# arduino_due_component_connection_2.net
KiCad netlist of a schematic drawn in Altium Designer
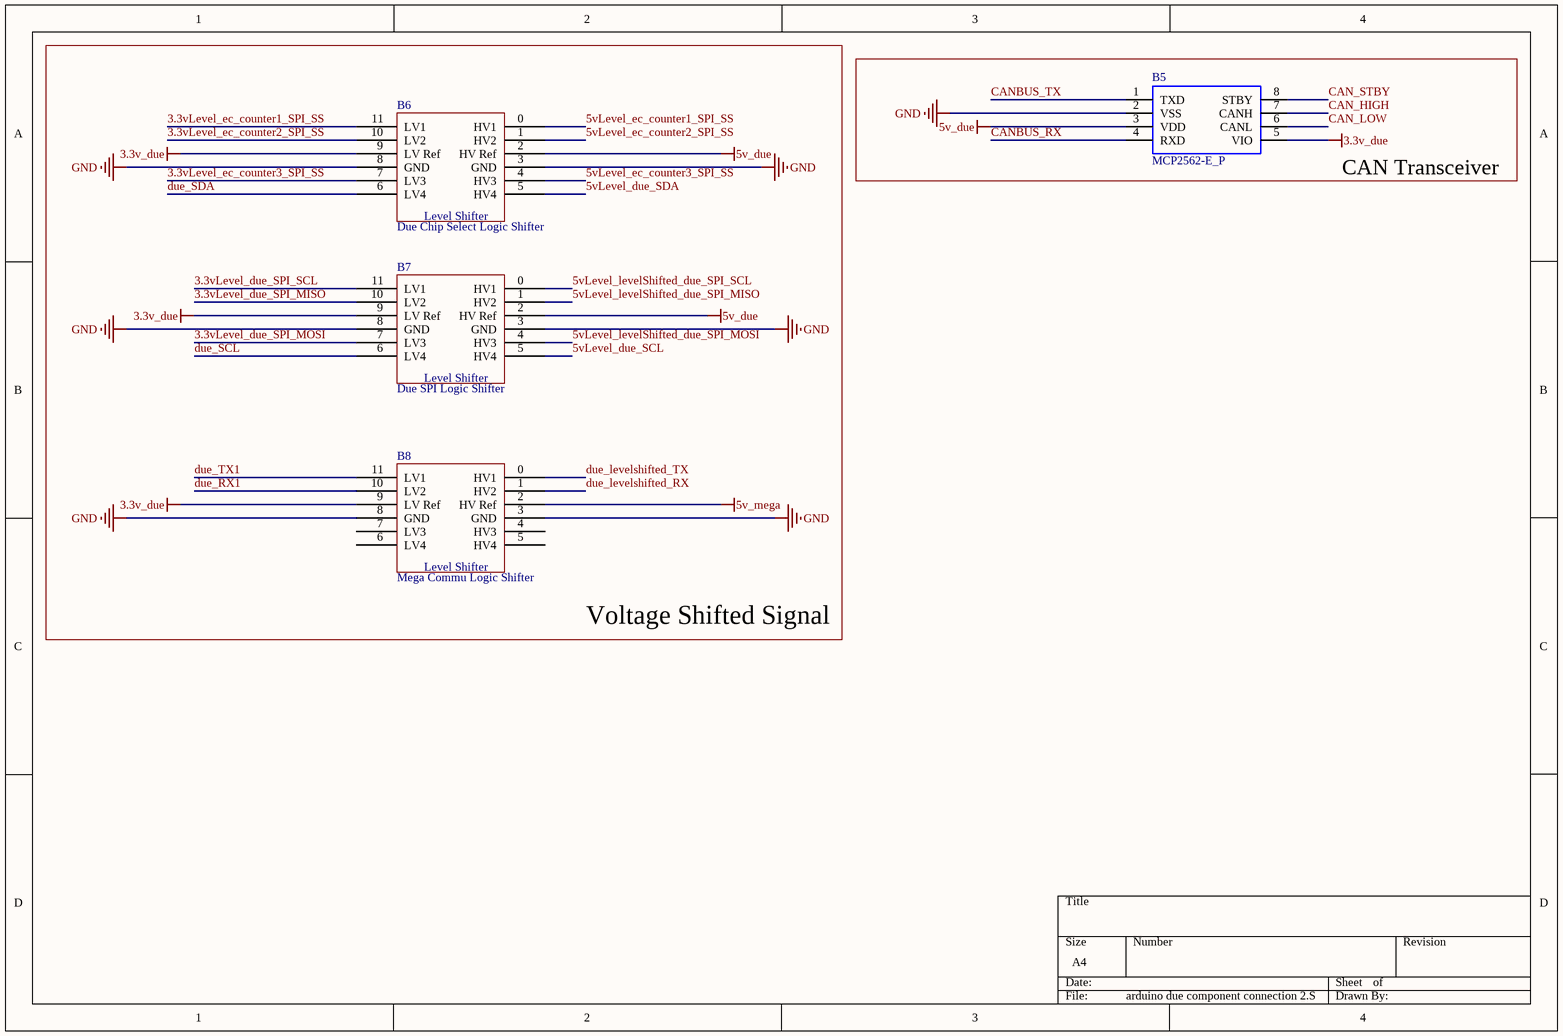
[diagram p0: arduino due component connection 2.SchDoc]

(export (version "E")
  (design (tool "Eeschema 10.0.6"))
  (components
    (comp (ref "B5")
      (value "MCP2562-E_P")
      (footprint "DIP781W56P254L950H533Q8N")
      (fields
        (field (name "RS PART NUMBER") "7990225")
        (field (name "MANUFACTURER_PART_NUMBER") "MCP2562-E/P")
      )
      (libsource (lib "MCP2562-E_P") (part "MCP2562-E_P"))
    )
    (comp (ref "B6")
      (value "Level Shifter 4 Channel")
      (footprint "level shifter 4C:level shifter 4C")
      (fields (field (name "USAGE") "Due Chip Select Logic Shifter"))
      (libsource (lib "level shifter 4C") (part "Level Shifter 4 Channel"))
    )
    (comp (ref "B7")
      (value "Level Shifter 4 Channel")
      (footprint "level shifter 4C:level shifter 4C")
      (fields (field (name "USAGE") "Due SPI Logic Shifter"))
      (libsource (lib "level shifter 4C") (part "Level Shifter 4 Channel"))
    )
    (comp (ref "B8")
      (value "Level Shifter 4 Channel")
      (footprint "level shifter 4C:level shifter 4C")
      (fields (field (name "USAGE") "Mega Commu Logic Shifter"))
      (libsource (lib "level shifter 4C") (part "Level Shifter 4 Channel"))
    )
  )
  (nets
    (net (code "1") (name "/3.3vLevel_due_SPI_MISO") (class "Default")
      (node (ref "B7") (pin "10") (pinfunction "LV2_10") (pintype "passive"))
    )
    (net (code "2") (name "/3.3vLevel_due_SPI_MOSI") (class "Default")
      (node (ref "B7") (pin "7") (pinfunction "LV3_7") (pintype "passive"))
    )
    (net (code "3") (name "/3.3vLevel_due_SPI_SCL") (class "Default")
      (node (ref "B7") (pin "11") (pinfunction "LV1_11") (pintype "passive"))
    )
    (net (code "4") (name "/3.3vLevel_ec_counter1_SPI_SS") (class "Default")
      (node (ref "B6") (pin "11") (pinfunction "LV1_11") (pintype "passive"))
    )
    (net (code "5") (name "/3.3vLevel_ec_counter2_SPI_SS") (class "Default")
      (node (ref "B6") (pin "10") (pinfunction "LV2_10") (pintype "passive"))
    )
    (net (code "6") (name "/3.3vLevel_ec_counter3_SPI_SS") (class "Default")
      (node (ref "B6") (pin "7") (pinfunction "LV3_7") (pintype "passive"))
    )
    (net (code "7") (name "/5vLevel_due_SCL") (class "Default")
      (node (ref "B7") (pin "5") (pinfunction "HV4_5") (pintype "passive"))
    )
    (net (code "8") (name "/5vLevel_due_SDA") (class "Default")
      (node (ref "B6") (pin "5") (pinfunction "HV4_5") (pintype "passive"))
    )
    (net (code "9") (name "/5vLevel_ec_counter1_SPI_SS") (class "Default")
      (node (ref "B6") (pin "0") (pinfunction "HV1_0") (pintype "passive"))
    )
    (net (code "10") (name "/5vLevel_ec_counter2_SPI_SS") (class "Default")
      (node (ref "B6") (pin "1") (pinfunction "HV2_1") (pintype "passive"))
    )
    (net (code "11") (name "/5vLevel_ec_counter3_SPI_SS") (class "Default")
      (node (ref "B6") (pin "4") (pinfunction "HV3_4") (pintype "passive"))
    )
    (net (code "12") (name "/5vLevel_levelShifted_due_SPI_MISO") (class "Default")
      (node (ref "B7") (pin "1") (pinfunction "HV2_1") (pintype "passive"))
    )
    (net (code "13") (name "/5vLevel_levelShifted_due_SPI_MOSI") (class "Default")
      (node (ref "B7") (pin "4") (pinfunction "HV3_4") (pintype "passive"))
    )
    (net (code "14") (name "/5vLevel_levelShifted_due_SPI_SCL") (class "Default")
      (node (ref "B7") (pin "0") (pinfunction "HV1_0") (pintype "passive"))
    )
    (net (code "15") (name "/CANBUS_RX") (class "Default")
      (node (ref "B5") (pin "4") (pinfunction "RXD_4") (pintype "passive"))
    )
    (net (code "16") (name "/CANBUS_TX") (class "Default")
      (node (ref "B5") (pin "1") (pinfunction "TXD_1") (pintype "passive"))
    )
    (net (code "17") (name "/CAN_HIGH") (class "Default")
      (node (ref "B5") (pin "7") (pinfunction "CANH_7") (pintype "passive"))
    )
    (net (code "18") (name "/CAN_LOW") (class "Default")
      (node (ref "B5") (pin "6") (pinfunction "CANL_6") (pintype "passive"))
    )
    (net (code "19") (name "/CAN_STBY") (class "Default")
      (node (ref "B5") (pin "8") (pinfunction "STBY_8") (pintype "passive"))
    )
    (net (code "20") (name "/due_RX1") (class "Default")
      (node (ref "B8") (pin "10") (pinfunction "LV2_10") (pintype "passive"))
    )
    (net (code "21") (name "/due_SCL") (class "Default")
      (node (ref "B7") (pin "6") (pinfunction "LV4_6") (pintype "passive"))
    )
    (net (code "22") (name "/due_SDA") (class "Default")
      (node (ref "B6") (pin "6") (pinfunction "LV4_6") (pintype "passive"))
    )
    (net (code "23") (name "/due_TX1") (class "Default")
      (node (ref "B8") (pin "11") (pinfunction "LV1_11") (pintype "passive"))
    )
    (net (code "24") (name "/due_levelshifted_RX") (class "Default")
      (node (ref "B8") (pin "1") (pinfunction "HV2_1") (pintype "passive"))
    )
    (net (code "25") (name "/due_levelshifted_TX") (class "Default")
      (node (ref "B8") (pin "0") (pinfunction "HV1_0") (pintype "passive"))
    )
    (net (code "26") (name "3.3v_due") (class "Default")
      (node (ref "B5") (pin "5") (pinfunction "VIO_5") (pintype "passive"))
      (node (ref "B6") (pin "9") (pinfunction "LV_Ref_9") (pintype "passive"))
      (node (ref "B7") (pin "9") (pinfunction "LV_Ref_9") (pintype "passive"))
      (node (ref "B8") (pin "9") (pinfunction "LV_Ref_9") (pintype "passive"))
    )
    (net (code "27") (name "5v_due") (class "Default")
      (node (ref "B5") (pin "3") (pinfunction "VDD_3") (pintype "passive"))
      (node (ref "B6") (pin "2") (pinfunction "HV_Ref_2") (pintype "passive"))
      (node (ref "B7") (pin "2") (pinfunction "HV_Ref_2") (pintype "passive"))
    )
    (net (code "28") (name "5v_mega") (class "Default")
      (node (ref "B8") (pin "2") (pinfunction "HV_Ref_2") (pintype "passive"))
    )
    (net (code "29") (name "GND") (class "Default")
      (node (ref "B5") (pin "2") (pinfunction "VSS_2") (pintype "passive"))
      (node (ref "B6") (pin "3") (pinfunction "GND_3") (pintype "passive"))
      (node (ref "B6") (pin "8") (pinfunction "GND_8") (pintype "passive"))
      (node (ref "B7") (pin "3") (pinfunction "GND_3") (pintype "passive"))
      (node (ref "B7") (pin "8") (pinfunction "GND_8") (pintype "passive"))
      (node (ref "B8") (pin "3") (pinfunction "GND_3") (pintype "passive"))
      (node (ref "B8") (pin "8") (pinfunction "GND_8") (pintype "passive"))
    )
    (net (code "30") (name "unconnected-(B8-HV3-Pad4)") (class "Default")
      (node (ref "B8") (pin "4") (pinfunction "HV3_4") (pintype "passive"))
    )
    (net (code "31") (name "unconnected-(B8-HV4-Pad5)") (class "Default")
      (node (ref "B8") (pin "5") (pinfunction "HV4_5") (pintype "passive"))
    )
    (net (code "32") (name "unconnected-(B8-LV3-Pad7)") (class "Default")
      (node (ref "B8") (pin "7") (pinfunction "LV3_7") (pintype "passive"))
    )
    (net (code "33") (name "unconnected-(B8-LV4-Pad6)") (class "Default")
      (node (ref "B8") (pin "6") (pinfunction "LV4_6") (pintype "passive"))
    )
  )
)
